# led_single_prototype_arduino_uno.net
KiCad netlist of a schematic drawn in EAGLE
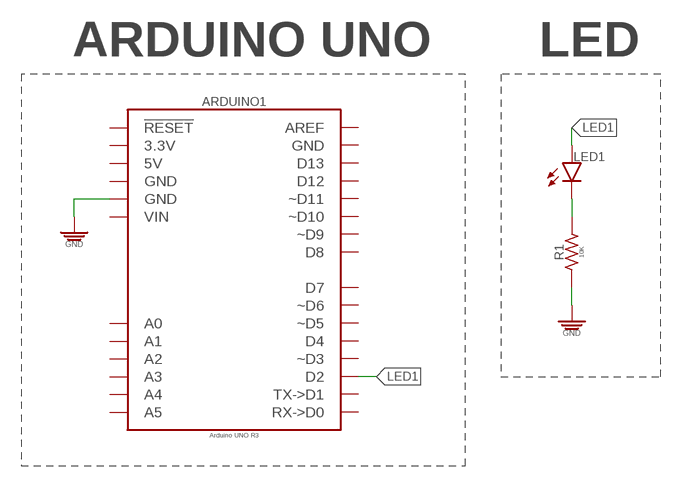
[diagram p0: schematic, sheet 1]

(export (version "E")
  (design (tool "Eeschema 10.0.6"))
  (components
    (comp (ref "ARDUINO1")
      (value "Arduino UNO R3")
      (footprint "eagle-import:ARDUINO_UNO_R3_NO-HOLES_NO-AVR-ISP_NO-I2C_NO-NC_NO-IOREF")
      (fields (field (name "MFR") "Arduino") (field (name "MPN") "A000066"))
      (libsource (lib "eagle-import") (part "ARDUINO_UNO_R3_NO-HOLES_NO-AVR-ISP_NO-I2C_NO-NC_NO-IOREF"))
    )
    (comp (ref "LED1")
      (value "LED_PTH_T-1_3/4_5MM_NO-COLOR")
      (footprint "eagle-import:LED_PTH_T-1_3_4_5MM")
      (libsource (lib "eagle-import") (part "LED_PTH_T-1_3/4_5MM_NO-COLOR"))
    )
    (comp (ref "R1")
      (value "10K")
      (footprint "eagle-import:RESAD660W45L340D190B")
      (fields (field (name "MFR") "Yageo") (field (name "MPN") "CFR-12JB-52-10K"))
      (libsource (lib "eagle-import") (part "10KΩ_PTH-204/7_1/6W-5%"))
    )
  )
  (nets
    (net (code "1") (name "GND") (class "Default")
      (node (ref "ARDUINO1") (pin "GND@2") (pinfunction "GND_GND@2") (pintype "bidirectional"))
      (node (ref "R1") (pin "1") (pinfunction "1_1") (pintype "passive"))
    )
    (net (code "2") (name "LED1") (class "Default")
      (node (ref "ARDUINO1") (pin "D2") (pinfunction "D2_D2") (pintype "bidirectional"))
      (node (ref "LED1") (pin "A") (pinfunction "A_A") (pintype "passive"))
    )
    (net (code "3") (name "Net-(LED1-PadK)") (class "Default")
      (node (ref "LED1") (pin "K") (pinfunction "K_K") (pintype "passive"))
      (node (ref "R1") (pin "2") (pinfunction "2_2") (pintype "passive"))
    )
    (net (code "4") (name "unconnected-(ARDUINO1-GND-PadGND@1)") (class "Default")
      (node (ref "ARDUINO1") (pin "GND@1") (pinfunction "GND_GND@1") (pintype "bidirectional"))
    )
    (net (code "5") (name "unconnected-(ARDUINO1-GND-PadGND@3)") (class "Default")
      (node (ref "ARDUINO1") (pin "GND@3") (pinfunction "GND_GND@3") (pintype "bidirectional"))
    )
    (net (code "6") (name "unconnected-(ARDUINO1-Pad3.3V)") (class "Default")
      (node (ref "ARDUINO1") (pin "3.3V") (pinfunction "3.3V_3.3V") (pintype "bidirectional"))
    )
    (net (code "7") (name "unconnected-(ARDUINO1-Pad5V)") (class "Default")
      (node (ref "ARDUINO1") (pin "5V") (pinfunction "5V_5V") (pintype "bidirectional"))
    )
    (net (code "8") (name "unconnected-(ARDUINO1-PadA0)") (class "Default")
      (node (ref "ARDUINO1") (pin "A0") (pinfunction "A0_A0") (pintype "bidirectional"))
    )
    (net (code "9") (name "unconnected-(ARDUINO1-PadA1)") (class "Default")
      (node (ref "ARDUINO1") (pin "A1") (pinfunction "A1_A1") (pintype "bidirectional"))
    )
    (net (code "10") (name "unconnected-(ARDUINO1-PadA2)") (class "Default")
      (node (ref "ARDUINO1") (pin "A2") (pinfunction "A2_A2") (pintype "bidirectional"))
    )
    (net (code "11") (name "unconnected-(ARDUINO1-PadA3)") (class "Default")
      (node (ref "ARDUINO1") (pin "A3") (pinfunction "A3_A3") (pintype "bidirectional"))
    )
    (net (code "12") (name "unconnected-(ARDUINO1-PadA4)") (class "Default")
      (node (ref "ARDUINO1") (pin "A4") (pinfunction "A4_A4") (pintype "bidirectional"))
    )
    (net (code "13") (name "unconnected-(ARDUINO1-PadA5)") (class "Default")
      (node (ref "ARDUINO1") (pin "A5") (pinfunction "A5_A5") (pintype "bidirectional"))
    )
    (net (code "14") (name "unconnected-(ARDUINO1-PadAREF)") (class "Default")
      (node (ref "ARDUINO1") (pin "AREF") (pinfunction "AREF_AREF") (pintype "bidirectional"))
    )
    (net (code "15") (name "unconnected-(ARDUINO1-PadD4)") (class "Default")
      (node (ref "ARDUINO1") (pin "D4") (pinfunction "D4_D4") (pintype "bidirectional"))
    )
    (net (code "16") (name "unconnected-(ARDUINO1-PadD7)") (class "Default")
      (node (ref "ARDUINO1") (pin "D7") (pinfunction "D7_D7") (pintype "bidirectional"))
    )
    (net (code "17") (name "unconnected-(ARDUINO1-PadD8)") (class "Default")
      (node (ref "ARDUINO1") (pin "D8") (pinfunction "D8_D8") (pintype "bidirectional"))
    )
    (net (code "18") (name "unconnected-(ARDUINO1-PadD12)") (class "Default")
      (node (ref "ARDUINO1") (pin "D12") (pinfunction "D12_D12") (pintype "bidirectional"))
    )
    (net (code "19") (name "unconnected-(ARDUINO1-PadD13)") (class "Default")
      (node (ref "ARDUINO1") (pin "D13") (pinfunction "D13_D13") (pintype "bidirectional"))
    )
    (net (code "20") (name "unconnected-(ARDUINO1-PadVIN)") (class "Default")
      (node (ref "ARDUINO1") (pin "VIN") (pinfunction "VIN_VIN") (pintype "bidirectional"))
    )
    (net (code "21") (name "unconnected-(ARDUINO1-RX->D0-PadD0)") (class "Default")
      (node (ref "ARDUINO1") (pin "D0") (pinfunction "RX->D0_D0") (pintype "bidirectional"))
    )
    (net (code "22") (name "unconnected-(ARDUINO1-TX->D1-PadD1)") (class "Default")
      (node (ref "ARDUINO1") (pin "D1") (pinfunction "TX->D1_D1") (pintype "bidirectional"))
    )
    (net (code "23") (name "unconnected-(ARDUINO1-~{D3}-PadD3)") (class "Default")
      (node (ref "ARDUINO1") (pin "D3") (pinfunction "~{D3}_D3") (pintype "bidirectional"))
    )
    (net (code "24") (name "unconnected-(ARDUINO1-~{D5}-PadD5)") (class "Default")
      (node (ref "ARDUINO1") (pin "D5") (pinfunction "~{D5}_D5") (pintype "bidirectional"))
    )
    (net (code "25") (name "unconnected-(ARDUINO1-~{D6}-PadD6)") (class "Default")
      (node (ref "ARDUINO1") (pin "D6") (pinfunction "~{D6}_D6") (pintype "bidirectional"))
    )
    (net (code "26") (name "unconnected-(ARDUINO1-~{D9}-PadD9)") (class "Default")
      (node (ref "ARDUINO1") (pin "D9") (pinfunction "~{D9}_D9") (pintype "bidirectional"))
    )
    (net (code "27") (name "unconnected-(ARDUINO1-~{D10}-PadD10)") (class "Default")
      (node (ref "ARDUINO1") (pin "D10") (pinfunction "~{D10}_D10") (pintype "bidirectional"))
    )
    (net (code "28") (name "unconnected-(ARDUINO1-~{D11}-PadD11)") (class "Default")
      (node (ref "ARDUINO1") (pin "D11") (pinfunction "~{D11}_D11") (pintype "bidirectional"))
    )
    (net (code "29") (name "unconnected-(ARDUINO1-~{RESET}-PadRESET@1)") (class "Default")
      (node (ref "ARDUINO1") (pin "RESET@1") (pinfunction "~{RESET}_RESET@1") (pintype "bidirectional"))
    )
  )
)
